# Display.net
KiCad netlist of a schematic drawn in Altium Designer
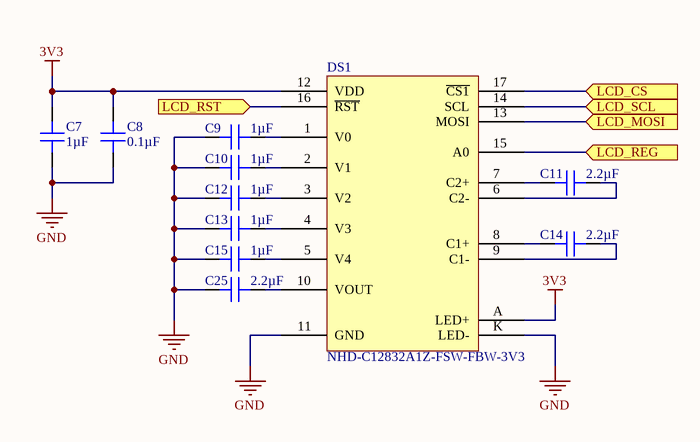
[diagram p0: Display.SchDoc]

(export (version "E")
  (design (tool "Eeschema 10.0.6"))
  (components
    (comp (ref "C7")
      (value "1µF")
      (footprint "CAP 0603_1608")
      (description "CAP CER 1UF 25V X5R 0603")
      (fields (field (name "PART NUMBER") "TMK107BJ105MAHT") (field (name "MANUFACTURER") "Taiyo Yuden"))
      (libsource (lib "Celestial Altium Library - altium_library") (part "Capacitor"))
    )
    (comp (ref "C8")
      (value "0.1µF")
      (footprint "CAP 0603_1608")
      (description "CAP CER 0.1UF 16V X7R 0603")
      (fields (field (name "PART NUMBER") "CS0603KRX7R7BB104") (field (name "MANUFACTURER") "Yageo"))
      (libsource (lib "Celestial Altium Library - altium_library") (part "Capacitor"))
    )
    (comp (ref "C9")
      (value "1µF")
      (footprint "CAP 0603_1608")
      (description "CAP CER 1UF 25V X5R 0603")
      (fields (field (name "PART NUMBER") "TMK107BJ105MAHT") (field (name "MANUFACTURER") "Taiyo Yuden"))
      (libsource (lib "Celestial Altium Library - altium_library") (part "Capacitor"))
    )
    (comp (ref "C10")
      (value "1µF")
      (footprint "CAP 0603_1608")
      (description "CAP CER 1UF 25V X5R 0603")
      (fields (field (name "PART NUMBER") "TMK107BJ105MAHT") (field (name "MANUFACTURER") "Taiyo Yuden"))
      (libsource (lib "Celestial Altium Library - altium_library") (part "Capacitor"))
    )
    (comp (ref "C11")
      (value "2.2µF")
      (footprint "CAP 0603_1608")
      (description "CAP CER 2.2UF 16V Y5V 0603")
      (fields (field (name "PART NUMBER") "CC0603ZRY5V7BB225") (field (name "MANUFACTURER") "Yageo"))
      (libsource (lib "Celestial Altium Library - altium_library") (part "Capacitor"))
    )
    (comp (ref "C12")
      (value "1µF")
      (footprint "CAP 0603_1608")
      (description "CAP CER 1UF 25V X5R 0603")
      (fields (field (name "PART NUMBER") "TMK107BJ105MAHT") (field (name "MANUFACTURER") "Taiyo Yuden"))
      (libsource (lib "Celestial Altium Library - altium_library") (part "Capacitor"))
    )
    (comp (ref "C13")
      (value "1µF")
      (footprint "CAP 0603_1608")
      (description "CAP CER 1UF 25V X5R 0603")
      (fields (field (name "PART NUMBER") "TMK107BJ105MAHT") (field (name "MANUFACTURER") "Taiyo Yuden"))
      (libsource (lib "Celestial Altium Library - altium_library") (part "Capacitor"))
    )
    (comp (ref "C14")
      (value "2.2µF")
      (footprint "CAP 0603_1608")
      (description "CAP CER 2.2UF 16V Y5V 0603")
      (fields (field (name "PART NUMBER") "CC0603ZRY5V7BB225") (field (name "MANUFACTURER") "Yageo"))
      (libsource (lib "Celestial Altium Library - altium_library") (part "Capacitor"))
    )
    (comp (ref "C15")
      (value "1µF")
      (footprint "CAP 0603_1608")
      (description "CAP CER 1UF 25V X5R 0603")
      (fields (field (name "PART NUMBER") "TMK107BJ105MAHT") (field (name "MANUFACTURER") "Taiyo Yuden"))
      (libsource (lib "Celestial Altium Library - altium_library") (part "Capacitor"))
    )
    (comp (ref "C25")
      (value "2.2µF")
      (footprint "CAP 0603_1608")
      (description "CAP CER 2.2UF 16V Y5V 0603")
      (fields (field (name "PART NUMBER") "CC0603ZRY5V7BB225") (field (name "MANUFACTURER") "Yageo"))
      (libsource (lib "Celestial Altium Library - altium_library") (part "Capacitor"))
    )
    (comp (ref "DS1")
      (value "NHD-C12832A1Z-FSW-FBW-3V3")
      (footprint "NHD-C12832A1Z WHITE")
      (description "LCD COG GRAPHIC 128X32")
      (fields (field (name "MANUFACTURER") "Newhaven Display Intl"))
      (libsource (lib "Celestial Altium Library - altium_library") (part "Newhaven NHD-C12832A1Z"))
    )
  )
  (nets
    (net (code "1") (name "/LCD_CS") (class "Default")
      (node (ref "DS1") (pin "17") (pinfunction "~{CS1}_17") (pintype "passive"))
    )
    (net (code "2") (name "/LCD_MOSI") (class "Default")
      (node (ref "DS1") (pin "13") (pinfunction "MOSI_13") (pintype "passive"))
    )
    (net (code "3") (name "/LCD_REG") (class "Default")
      (node (ref "DS1") (pin "15") (pinfunction "A0_15") (pintype "passive"))
    )
    (net (code "4") (name "/LCD_RST") (class "Default")
      (node (ref "DS1") (pin "16") (pinfunction "~{RST}_16") (pintype "passive"))
    )
    (net (code "5") (name "/LCD_SCL") (class "Default")
      (node (ref "DS1") (pin "14") (pinfunction "SCL_14") (pintype "passive"))
    )
    (net (code "6") (name "3V3") (class "Default")
      (node (ref "C7") (pin "2") (pinfunction "2_2") (pintype "passive"))
      (node (ref "C8") (pin "2") (pinfunction "2_2") (pintype "passive"))
      (node (ref "DS1") (pin "12") (pinfunction "VDD_12") (pintype "passive"))
      (node (ref "DS1") (pin "A") (pinfunction "LED+_A") (pintype "passive"))
    )
    (net (code "7") (name "GND") (class "Default")
      (node (ref "C10") (pin "2") (pinfunction "2_2") (pintype "passive"))
      (node (ref "C12") (pin "2") (pinfunction "2_2") (pintype "passive"))
      (node (ref "C13") (pin "2") (pinfunction "2_2") (pintype "passive"))
      (node (ref "C15") (pin "2") (pinfunction "2_2") (pintype "passive"))
      (node (ref "C25") (pin "1") (pinfunction "1_1") (pintype "passive"))
      (node (ref "C7") (pin "1") (pinfunction "1_1") (pintype "passive"))
      (node (ref "C8") (pin "1") (pinfunction "1_1") (pintype "passive"))
      (node (ref "C9") (pin "2") (pinfunction "2_2") (pintype "passive"))
      (node (ref "DS1") (pin "11") (pinfunction "GND_11") (pintype "passive"))
      (node (ref "DS1") (pin "K") (pinfunction "LED-_K") (pintype "passive"))
    )
    (net (code "8") (name "Net-(DS1-C1+)") (class "Default")
      (node (ref "C14") (pin "1") (pinfunction "1_1") (pintype "passive"))
      (node (ref "DS1") (pin "8") (pinfunction "C1+_8") (pintype "passive"))
    )
    (net (code "9") (name "Net-(DS1-C1-)") (class "Default")
      (node (ref "C14") (pin "2") (pinfunction "2_2") (pintype "passive"))
      (node (ref "DS1") (pin "9") (pinfunction "C1-_9") (pintype "passive"))
    )
    (net (code "10") (name "Net-(DS1-C2+)") (class "Default")
      (node (ref "C11") (pin "1") (pinfunction "1_1") (pintype "passive"))
      (node (ref "DS1") (pin "7") (pinfunction "C2+_7") (pintype "passive"))
    )
    (net (code "11") (name "Net-(DS1-C2-)") (class "Default")
      (node (ref "C11") (pin "2") (pinfunction "2_2") (pintype "passive"))
      (node (ref "DS1") (pin "6") (pinfunction "C2-_6") (pintype "passive"))
    )
    (net (code "12") (name "Net-(DS1-V0)") (class "Default")
      (node (ref "C9") (pin "1") (pinfunction "1_1") (pintype "passive"))
      (node (ref "DS1") (pin "1") (pinfunction "V0_1") (pintype "passive"))
    )
    (net (code "13") (name "Net-(DS1-V1)") (class "Default")
      (node (ref "C10") (pin "1") (pinfunction "1_1") (pintype "passive"))
      (node (ref "DS1") (pin "2") (pinfunction "V1_2") (pintype "passive"))
    )
    (net (code "14") (name "Net-(DS1-V2)") (class "Default")
      (node (ref "C12") (pin "1") (pinfunction "1_1") (pintype "passive"))
      (node (ref "DS1") (pin "3") (pinfunction "V2_3") (pintype "passive"))
    )
    (net (code "15") (name "Net-(DS1-V3)") (class "Default")
      (node (ref "C13") (pin "1") (pinfunction "1_1") (pintype "passive"))
      (node (ref "DS1") (pin "4") (pinfunction "V3_4") (pintype "passive"))
    )
    (net (code "16") (name "Net-(DS1-V4)") (class "Default")
      (node (ref "C15") (pin "1") (pinfunction "1_1") (pintype "passive"))
      (node (ref "DS1") (pin "5") (pinfunction "V4_5") (pintype "passive"))
    )
    (net (code "17") (name "Net-(DS1-VOUT)") (class "Default")
      (node (ref "C25") (pin "2") (pinfunction "2_2") (pintype "passive"))
      (node (ref "DS1") (pin "10") (pinfunction "VOUT_10") (pintype "passive"))
    )
  )
)
